# MOTOR_V1_1.net
KiCad netlist of a schematic drawn in Altium Designer
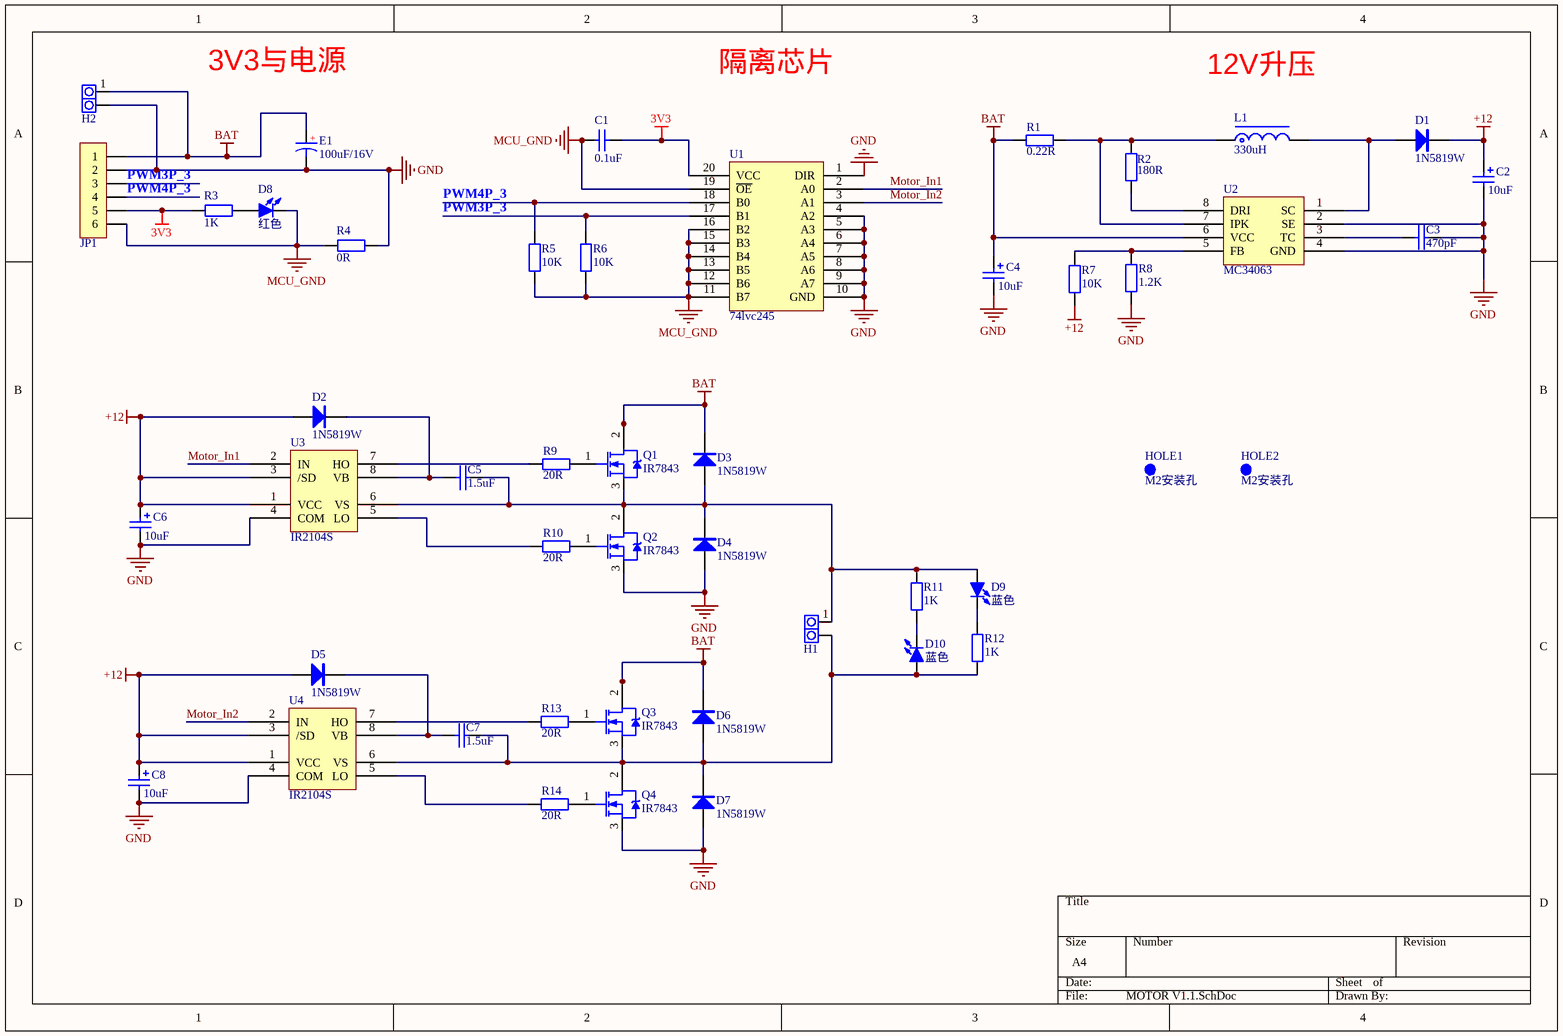
[diagram p0: MOTOR V1.1.SchDoc]

(export (version "E")
  (design (tool "Eeschema 10.0.6"))
  (components
    (comp (ref "C1")
      (value "0.1uF")
      (footprint "C0603_M")
      (description "贴片电容")
      (libsource (lib "0.1 - 电阻-电容-电感-电位器") (part "C"))
    )
    (comp (ref "C2")
      (value "10uF")
      (footprint "C_3216")
      (description "Polarized Capacitor (Radial)")
      (fields (field (name "PUBLISHER") "Altium Limited"))
      (libsource (lib "EX_MOTOR") (part "Cap Pol1"))
    )
    (comp (ref "C3")
      (value "470pF")
      (footprint "R0603_M")
      (description "Capacitor")
      (libsource (lib "EX_MOTOR") (part "Cap"))
    )
    (comp (ref "C4")
      (value "10uF")
      (footprint "C_3216")
      (description "Polarized Capacitor (Radial)")
      (fields (field (name "PUBLISHER") "Altium Limited"))
      (libsource (lib "EX_MOTOR") (part "Cap Pol1"))
    )
    (comp (ref "C5")
      (value "1.5uF")
      (footprint "R1206_M")
      (description "Capacitor")
      (libsource (lib "EX_MOTOR") (part "Cap"))
    )
    (comp (ref "C6")
      (value "10uF")
      (footprint "C_3216")
      (description "Polarized Capacitor (Radial)")
      (fields (field (name "PUBLISHER") "Altium Limited"))
      (libsource (lib "EX_MOTOR") (part "Cap Pol1"))
    )
    (comp (ref "C7")
      (value "1.5uF")
      (footprint "R1206_M")
      (description "Capacitor")
      (libsource (lib "EX_MOTOR") (part "Cap"))
    )
    (comp (ref "C8")
      (value "10uF")
      (footprint "C_3216")
      (description "Polarized Capacitor (Radial)")
      (fields (field (name "PUBLISHER") "Altium Limited"))
      (libsource (lib "EX_MOTOR") (part "Cap Pol1"))
    )
    (comp (ref "D1")
      (value "1N5819W")
      (footprint "SOD-123")
      (description "肖特基二极管")
      (libsource (lib "0.2 - 二极管-TVS-整流桥") (part "1N5822"))
    )
    (comp (ref "D2")
      (value "1N5819W")
      (footprint "SOD-123")
      (description "肖特基二极管")
      (libsource (lib "0.2 - 二极管-TVS-整流桥") (part "1N5822"))
    )
    (comp (ref "D3")
      (value "1N5819W")
      (footprint "SOD-123")
      (description "肖特基二极管")
      (libsource (lib "0.2 - 二极管-TVS-整流桥") (part "1N5822"))
    )
    (comp (ref "D4")
      (value "1N5819W")
      (footprint "SOD-123")
      (description "肖特基二极管")
      (libsource (lib "0.2 - 二极管-TVS-整流桥") (part "1N5822"))
    )
    (comp (ref "D5")
      (value "1N5819W")
      (footprint "SOD-123")
      (description "肖特基二极管")
      (libsource (lib "0.2 - 二极管-TVS-整流桥") (part "1N5822"))
    )
    (comp (ref "D6")
      (value "1N5819W")
      (footprint "SOD-123")
      (description "肖特基二极管")
      (libsource (lib "0.2 - 二极管-TVS-整流桥") (part "1N5822"))
    )
    (comp (ref "D7")
      (value "1N5819W")
      (footprint "SOD-123")
      (description "肖特基二极管")
      (libsource (lib "0.2 - 二极管-TVS-整流桥") (part "1N5822"))
    )
    (comp (ref "D8")
      (value "红色")
      (footprint "LED0603_B")
      (description "贴片LED")
      (libsource (lib "0.3 - LED发光二极管") (part "LED-SMD"))
    )
    (comp (ref "D9")
      (value "蓝色")
      (footprint "LED0603_B")
      (description "贴片LED")
      (libsource (lib "0.3 - LED发光二极管") (part "LED-SMD"))
    )
    (comp (ref "D10")
      (value "蓝色")
      (footprint "LED0603_B")
      (description "贴片LED")
      (libsource (lib "0.3 - LED发光二极管") (part "LED-SMD"))
    )
    (comp (ref "E1")
      (value "100uF/16V")
      (footprint "CS 5*6 - B")
      (description "贴片固态电容")
      (libsource (lib "0.1 - 电阻-电容-电感-电位器") (part "CS_SMD"))
    )
    (comp (ref "H1")
      (value "PAD2")
      (footprint "PAD2-5.08")
      (description "引线焊盘")
      (libsource (lib "0.7 - 常用按键-开关-蜂鸣器-电池-测试点") (part "PAD2"))
    )
    (comp (ref "H2")
      (value "PAD2")
      (footprint "PAD2-5.08")
      (description "引线焊盘")
      (libsource (lib "0.7 - 常用按键-开关-蜂鸣器-电池-测试点") (part "PAD2"))
    )
    (comp (ref "HOLE1") (value "M2安装孔") (footprint "M2安装孔") (libsource (lib "base") (part "M2安装孔")))
    (comp (ref "HOLE2") (value "M2安装孔") (footprint "M2安装孔") (libsource (lib "base") (part "M2安装孔")))
    (comp (ref "JP1")
      (value "HDR-1X6")
      (footprint "XH2.54-WI-6P")
      (description "6P接插件")
      (libsource (lib "5.4 - 接插件-脚距2.54 (100mil) ") (part "Header 6"))
    )
    (comp (ref "L1")
      (value "330uH")
      (footprint "功率电感")
      (description "CDRH功率屏蔽电感")
      (libsource (lib "0.1 - 电阻-电容-电感-电位器") (part "L-CDRH"))
    )
    (comp (ref "Q1")
      (value "IR7843")
      (footprint "TO-252  mos管")
      (description "N-Channel Power MOSFET")
      (fields (field (name "PUBLISHER") "Altium Limited"))
      (libsource (lib "EX_MOTOR") (part "NMOS-2"))
    )
    (comp (ref "Q2")
      (value "IR7843")
      (footprint "TO-252  mos管")
      (description "N-Channel Power MOSFET")
      (fields (field (name "PUBLISHER") "Altium Limited"))
      (libsource (lib "EX_MOTOR") (part "NMOS-2"))
    )
    (comp (ref "Q3")
      (value "IR7843")
      (footprint "TO-252  mos管")
      (description "N-Channel Power MOSFET")
      (fields (field (name "PUBLISHER") "Altium Limited"))
      (libsource (lib "EX_MOTOR") (part "NMOS-2"))
    )
    (comp (ref "Q4")
      (value "IR7843")
      (footprint "TO-252  mos管")
      (description "N-Channel Power MOSFET")
      (fields (field (name "PUBLISHER") "Altium Limited"))
      (libsource (lib "EX_MOTOR") (part "NMOS-2"))
    )
    (comp (ref "R1")
      (value "0.22R")
      (footprint "R0603_M")
      (description "Resistor")
      (fields (field (name "PUBLISHER") "Altium Limited"))
      (libsource (lib "EX_MOTOR") (part "Res2"))
    )
    (comp (ref "R2")
      (value "180R")
      (footprint "R0603_M")
      (description "Resistor")
      (fields (field (name "PUBLISHER") "Altium Limited"))
      (libsource (lib "") (part "Res2_1"))
    )
    (comp (ref "R3")
      (value "1K")
      (footprint "R0603_M")
      (description "贴片电阻")
      (libsource (lib "0.1 - 电阻-电容-电感-电位器") (part "R"))
    )
    (comp (ref "R4")
      (value "0R")
      (footprint "R0603_M")
      (description "贴片电阻")
      (libsource (lib "0.1 - 电阻-电容-电感-电位器") (part "R"))
    )
    (comp (ref "R5")
      (value "10K")
      (footprint "R0603_M")
      (description "贴片电阻")
      (libsource (lib "0.1 - 电阻-电容-电感-电位器") (part "R"))
    )
    (comp (ref "R6")
      (value "10K")
      (footprint "R0603_M")
      (description "贴片电阻")
      (libsource (lib "0.1 - 电阻-电容-电感-电位器") (part "R"))
    )
    (comp (ref "R7")
      (value "10K")
      (footprint "R0603_M")
      (description "贴片电阻")
      (libsource (lib "0.1 - 电阻-电容-电感-电位器") (part "R"))
    )
    (comp (ref "R8")
      (value "1.2K")
      (footprint "R0603_M")
      (description "贴片电阻")
      (libsource (lib "0.1 - 电阻-电容-电感-电位器") (part "R"))
    )
    (comp (ref "R9")
      (value "20R")
      (footprint "R0603_M")
      (description "Resistor")
      (fields (field (name "PUBLISHER") "Altium Limited"))
      (libsource (lib "EX_MOTOR") (part "Res2"))
    )
    (comp (ref "R10")
      (value "20R")
      (footprint "R0603_M")
      (description "Resistor")
      (fields (field (name "PUBLISHER") "Altium Limited"))
      (libsource (lib "EX_MOTOR") (part "Res2"))
    )
    (comp (ref "R11")
      (value "1K")
      (footprint "R0603_M")
      (description "贴片电阻")
      (libsource (lib "0.1 - 电阻-电容-电感-电位器") (part "R"))
    )
    (comp (ref "R12")
      (value "1K")
      (footprint "R0603_M")
      (description "贴片电阻")
      (libsource (lib "0.1 - 电阻-电容-电感-电位器") (part "R"))
    )
    (comp (ref "R13")
      (value "20R")
      (footprint "R0603_M")
      (description "Resistor")
      (fields (field (name "PUBLISHER") "Altium Limited"))
      (libsource (lib "EX_MOTOR") (part "Res2"))
    )
    (comp (ref "R14")
      (value "20R")
      (footprint "R0603_M")
      (description "Resistor")
      (fields (field (name "PUBLISHER") "Altium Limited"))
      (libsource (lib "EX_MOTOR") (part "Res2"))
    )
    (comp (ref "U1")
      (value "74lvc245")
      (footprint "TSSOP20_M")
      (description "8位5伏转3.3伏电平转换芯片")
      (libsource (lib "EX_MOTOR") (part "74lvc245"))
    )
    (comp (ref "U2") (value "MC34063") (footprint "SO8NB") (libsource (lib "EX_MOTOR") (part "MC34063")))
    (comp (ref "U3") (value "IR2104S") (footprint "SO8NB") (libsource (lib "EX_MOTOR") (part "IR2104S")))
    (comp (ref "U4") (value "IR2104S") (footprint "SO8NB") (libsource (lib "EX_MOTOR") (part "IR2104S")))
  )
  (nets
    (net (code "1") (name "+12") (class "Default")
      (node (ref "C2") (pin "1") (pinfunction "1_1") (pintype "passive"))
      (node (ref "C6") (pin "1") (pinfunction "1_1") (pintype "passive"))
      (node (ref "C8") (pin "1") (pinfunction "1_1") (pintype "passive"))
      (node (ref "D1") (pin "2") (pinfunction "K_2") (pintype "passive"))
      (node (ref "D2") (pin "1") (pinfunction "A_1") (pintype "passive"))
      (node (ref "D5") (pin "1") (pinfunction "A_1") (pintype "passive"))
      (node (ref "R7") (pin "1") (pinfunction "1_1") (pintype "passive"))
      (node (ref "U3") (pin "1") (pinfunction "VCC_1") (pintype "passive"))
      (node (ref "U3") (pin "3") (pinfunction "/SD_3") (pintype "passive"))
      (node (ref "U4") (pin "1") (pinfunction "VCC_1") (pintype "passive"))
      (node (ref "U4") (pin "3") (pinfunction "/SD_3") (pintype "passive"))
    )
    (net (code "2") (name "/Motor_In1") (class "Default")
      (node (ref "U1") (pin "2") (pinfunction "A0_2") (pintype "passive"))
      (node (ref "U3") (pin "2") (pinfunction "IN_2") (pintype "passive"))
    )
    (net (code "3") (name "/Motor_In2") (class "Default")
      (node (ref "U1") (pin "3") (pinfunction "A1_3") (pintype "passive"))
      (node (ref "U4") (pin "2") (pinfunction "IN_2") (pintype "passive"))
    )
    (net (code "4") (name "/PWM3P_3") (class "Default")
      (node (ref "JP1") (pin "3") (pinfunction "3_3") (pintype "passive"))
      (node (ref "R6") (pin "2") (pinfunction "2_2") (pintype "passive"))
      (node (ref "U1") (pin "17") (pinfunction "B1_17") (pintype "passive"))
    )
    (net (code "5") (name "/PWM4P_3") (class "Default")
      (node (ref "JP1") (pin "4") (pinfunction "4_4") (pintype "passive"))
      (node (ref "R5") (pin "2") (pinfunction "2_2") (pintype "passive"))
      (node (ref "U1") (pin "18") (pinfunction "B0_18") (pintype "passive"))
    )
    (net (code "6") (name "3V3") (class "Default")
      (node (ref "C1") (pin "1") (pinfunction "1_1") (pintype "passive"))
      (node (ref "JP1") (pin "5") (pinfunction "5_5") (pintype "passive"))
      (node (ref "R3") (pin "2") (pinfunction "2_2") (pintype "passive"))
      (node (ref "U1") (pin "20") (pinfunction "VCC_20") (pintype "passive"))
    )
    (net (code "7") (name "BAT") (class "Default")
      (node (ref "C4") (pin "1") (pinfunction "1_1") (pintype "passive"))
      (node (ref "D3") (pin "2") (pinfunction "K_2") (pintype "passive"))
      (node (ref "D6") (pin "2") (pinfunction "K_2") (pintype "passive"))
      (node (ref "E1") (pin "1") (pinfunction "1_1") (pintype "passive"))
      (node (ref "H2") (pin "1") (pinfunction "1_1") (pintype "passive"))
      (node (ref "JP1") (pin "1") (pinfunction "1_1") (pintype "passive"))
      (node (ref "Q1") (pin "2") (pinfunction "D_2") (pintype "passive"))
      (node (ref "Q3") (pin "2") (pinfunction "D_2") (pintype "passive"))
      (node (ref "R1") (pin "1") (pinfunction "1_1") (pintype "passive"))
      (node (ref "U2") (pin "6") (pinfunction "VCC_6") (pintype "passive"))
    )
    (net (code "8") (name "GND") (class "Default")
      (node (ref "C2") (pin "2") (pinfunction "2_2") (pintype "passive"))
      (node (ref "C3") (pin "2") (pinfunction "2_2") (pintype "passive"))
      (node (ref "C4") (pin "2") (pinfunction "2_2") (pintype "passive"))
      (node (ref "C6") (pin "2") (pinfunction "2_2") (pintype "passive"))
      (node (ref "C8") (pin "2") (pinfunction "2_2") (pintype "passive"))
      (node (ref "D4") (pin "1") (pinfunction "A_1") (pintype "passive"))
      (node (ref "D7") (pin "1") (pinfunction "A_1") (pintype "passive"))
      (node (ref "E1") (pin "2") (pinfunction "2_2") (pintype "passive"))
      (node (ref "H2") (pin "2") (pinfunction "2_2") (pintype "passive"))
      (node (ref "JP1") (pin "2") (pinfunction "2_2") (pintype "passive"))
      (node (ref "Q2") (pin "3") (pinfunction "S_3") (pintype "passive"))
      (node (ref "Q4") (pin "3") (pinfunction "S_3") (pintype "passive"))
      (node (ref "R4") (pin "2") (pinfunction "2_2") (pintype "passive"))
      (node (ref "R8") (pin "1") (pinfunction "1_1") (pintype "passive"))
      (node (ref "U1") (pin "1") (pinfunction "DIR_1") (pintype "passive"))
      (node (ref "U1") (pin "10") (pinfunction "GND_10") (pintype "passive"))
      (node (ref "U1") (pin "4") (pinfunction "A2_4") (pintype "passive"))
      (node (ref "U1") (pin "5") (pinfunction "A3_5") (pintype "passive"))
      (node (ref "U1") (pin "6") (pinfunction "A4_6") (pintype "passive"))
      (node (ref "U1") (pin "7") (pinfunction "A5_7") (pintype "passive"))
      (node (ref "U1") (pin "8") (pinfunction "A6_8") (pintype "passive"))
      (node (ref "U1") (pin "9") (pinfunction "A7_9") (pintype "passive"))
      (node (ref "U2") (pin "2") (pinfunction "SE_2") (pintype "passive"))
      (node (ref "U2") (pin "4") (pinfunction "GND_4") (pintype "passive"))
      (node (ref "U3") (pin "4") (pinfunction "COM_4") (pintype "passive"))
      (node (ref "U4") (pin "4") (pinfunction "COM_4") (pintype "passive"))
    )
    (net (code "9") (name "MCU_GND") (class "Default")
      (node (ref "C1") (pin "2") (pinfunction "2_2") (pintype "passive"))
      (node (ref "D8") (pin "2") (pinfunction "K_2") (pintype "passive"))
      (node (ref "JP1") (pin "6") (pinfunction "6_6") (pintype "passive"))
      (node (ref "R4") (pin "1") (pinfunction "1_1") (pintype "passive"))
      (node (ref "R5") (pin "1") (pinfunction "1_1") (pintype "passive"))
      (node (ref "R6") (pin "1") (pinfunction "1_1") (pintype "passive"))
      (node (ref "U1") (pin "11") (pinfunction "B7_11") (pintype "passive"))
      (node (ref "U1") (pin "12") (pinfunction "B6_12") (pintype "passive"))
      (node (ref "U1") (pin "13") (pinfunction "B5_13") (pintype "passive"))
      (node (ref "U1") (pin "14") (pinfunction "B4_14") (pintype "passive"))
      (node (ref "U1") (pin "15") (pinfunction "B3_15") (pintype "passive"))
      (node (ref "U1") (pin "16") (pinfunction "B2_16") (pintype "passive"))
      (node (ref "U1") (pin "19") (pinfunction "~{OE}_19") (pintype "passive"))
    )
    (net (code "10") (name "Net-(D1-A)") (class "Default")
      (node (ref "D1") (pin "1") (pinfunction "A_1") (pintype "passive"))
      (node (ref "L1") (pin "2") (pinfunction "2_2") (pintype "passive"))
      (node (ref "U2") (pin "1") (pinfunction "SC_1") (pintype "passive"))
    )
    (net (code "11") (name "Net-(D2-K)") (class "Default")
      (node (ref "C5") (pin "1") (pinfunction "1_1") (pintype "passive"))
      (node (ref "D2") (pin "2") (pinfunction "K_2") (pintype "passive"))
      (node (ref "U3") (pin "8") (pinfunction "VB_8") (pintype "passive"))
    )
    (net (code "12") (name "Net-(D3-A)") (class "Default")
      (node (ref "C5") (pin "2") (pinfunction "2_2") (pintype "passive"))
      (node (ref "D3") (pin "1") (pinfunction "A_1") (pintype "passive"))
      (node (ref "D4") (pin "2") (pinfunction "K_2") (pintype "passive"))
      (node (ref "D9") (pin "1") (pinfunction "A_1") (pintype "passive"))
      (node (ref "H1") (pin "1") (pinfunction "1_1") (pintype "passive"))
      (node (ref "Q1") (pin "3") (pinfunction "S_3") (pintype "passive"))
      (node (ref "Q2") (pin "2") (pinfunction "D_2") (pintype "passive"))
      (node (ref "R11") (pin "2") (pinfunction "2_2") (pintype "passive"))
      (node (ref "U3") (pin "6") (pinfunction "VS_6") (pintype "passive"))
    )
    (net (code "13") (name "Net-(D5-K)") (class "Default")
      (node (ref "C7") (pin "1") (pinfunction "1_1") (pintype "passive"))
      (node (ref "D5") (pin "2") (pinfunction "K_2") (pintype "passive"))
      (node (ref "U4") (pin "8") (pinfunction "VB_8") (pintype "passive"))
    )
    (net (code "14") (name "Net-(D8-A)") (class "Default")
      (node (ref "D8") (pin "1") (pinfunction "A_1") (pintype "passive"))
      (node (ref "R3") (pin "1") (pinfunction "1_1") (pintype "passive"))
    )
    (net (code "15") (name "Net-(D9-K)") (class "Default")
      (node (ref "D9") (pin "2") (pinfunction "K_2") (pintype "passive"))
      (node (ref "R12") (pin "1") (pinfunction "1_1") (pintype "passive"))
    )
    (net (code "16") (name "Net-(D10-A)") (class "Default")
      (node (ref "C7") (pin "2") (pinfunction "2_2") (pintype "passive"))
      (node (ref "D10") (pin "1") (pinfunction "A_1") (pintype "passive"))
      (node (ref "D6") (pin "1") (pinfunction "A_1") (pintype "passive"))
      (node (ref "D7") (pin "2") (pinfunction "K_2") (pintype "passive"))
      (node (ref "H1") (pin "2") (pinfunction "2_2") (pintype "passive"))
      (node (ref "Q3") (pin "3") (pinfunction "S_3") (pintype "passive"))
      (node (ref "Q4") (pin "2") (pinfunction "D_2") (pintype "passive"))
      (node (ref "R12") (pin "2") (pinfunction "2_2") (pintype "passive"))
      (node (ref "U4") (pin "6") (pinfunction "VS_6") (pintype "passive"))
    )
    (net (code "17") (name "Net-(D10-K)") (class "Default")
      (node (ref "D10") (pin "2") (pinfunction "K_2") (pintype "passive"))
      (node (ref "R11") (pin "1") (pinfunction "1_1") (pintype "passive"))
    )
    (net (code "18") (name "Net-(Q1-G)") (class "Default")
      (node (ref "Q1") (pin "1") (pinfunction "G_1") (pintype "passive"))
      (node (ref "R9") (pin "2") (pinfunction "2_2") (pintype "passive"))
    )
    (net (code "19") (name "Net-(Q2-G)") (class "Default")
      (node (ref "Q2") (pin "1") (pinfunction "G_1") (pintype "passive"))
      (node (ref "R10") (pin "2") (pinfunction "2_2") (pintype "passive"))
    )
    (net (code "20") (name "Net-(Q3-G)") (class "Default")
      (node (ref "Q3") (pin "1") (pinfunction "G_1") (pintype "passive"))
      (node (ref "R13") (pin "2") (pinfunction "2_2") (pintype "passive"))
    )
    (net (code "21") (name "Net-(Q4-G)") (class "Default")
      (node (ref "Q4") (pin "1") (pinfunction "G_1") (pintype "passive"))
      (node (ref "R14") (pin "2") (pinfunction "2_2") (pintype "passive"))
    )
    (net (code "22") (name "Net-(U2-DRI)") (class "Default")
      (node (ref "R2") (pin "1") (pinfunction "1_1") (pintype "passive"))
      (node (ref "U2") (pin "8") (pinfunction "DRI_8") (pintype "passive"))
    )
    (net (code "23") (name "Net-(U2-FB)") (class "Default")
      (node (ref "R7") (pin "2") (pinfunction "2_2") (pintype "passive"))
      (node (ref "R8") (pin "2") (pinfunction "2_2") (pintype "passive"))
      (node (ref "U2") (pin "5") (pinfunction "FB_5") (pintype "passive"))
    )
    (net (code "24") (name "Net-(U2-IPK)") (class "Default")
      (node (ref "L1") (pin "1") (pinfunction "1_1") (pintype "passive"))
      (node (ref "R1") (pin "2") (pinfunction "2_2") (pintype "passive"))
      (node (ref "R2") (pin "2") (pinfunction "2_2") (pintype "passive"))
      (node (ref "U2") (pin "7") (pinfunction "IPK_7") (pintype "passive"))
    )
    (net (code "25") (name "Net-(U2-TC)") (class "Default")
      (node (ref "C3") (pin "1") (pinfunction "1_1") (pintype "passive"))
      (node (ref "U2") (pin "3") (pinfunction "TC_3") (pintype "passive"))
    )
    (net (code "26") (name "Net-(U3-HO)") (class "Default")
      (node (ref "R9") (pin "1") (pinfunction "1_1") (pintype "passive"))
      (node (ref "U3") (pin "7") (pinfunction "HO_7") (pintype "passive"))
    )
    (net (code "27") (name "Net-(U3-LO)") (class "Default")
      (node (ref "R10") (pin "1") (pinfunction "1_1") (pintype "passive"))
      (node (ref "U3") (pin "5") (pinfunction "LO_5") (pintype "passive"))
    )
    (net (code "28") (name "Net-(U4-HO)") (class "Default")
      (node (ref "R13") (pin "1") (pinfunction "1_1") (pintype "passive"))
      (node (ref "U4") (pin "7") (pinfunction "HO_7") (pintype "passive"))
    )
    (net (code "29") (name "Net-(U4-LO)") (class "Default")
      (node (ref "R14") (pin "1") (pinfunction "1_1") (pintype "passive"))
      (node (ref "U4") (pin "5") (pinfunction "LO_5") (pintype "passive"))
    )
  )
)
